# WRIST.net
KiCad netlist of a schematic drawn in EAGLE
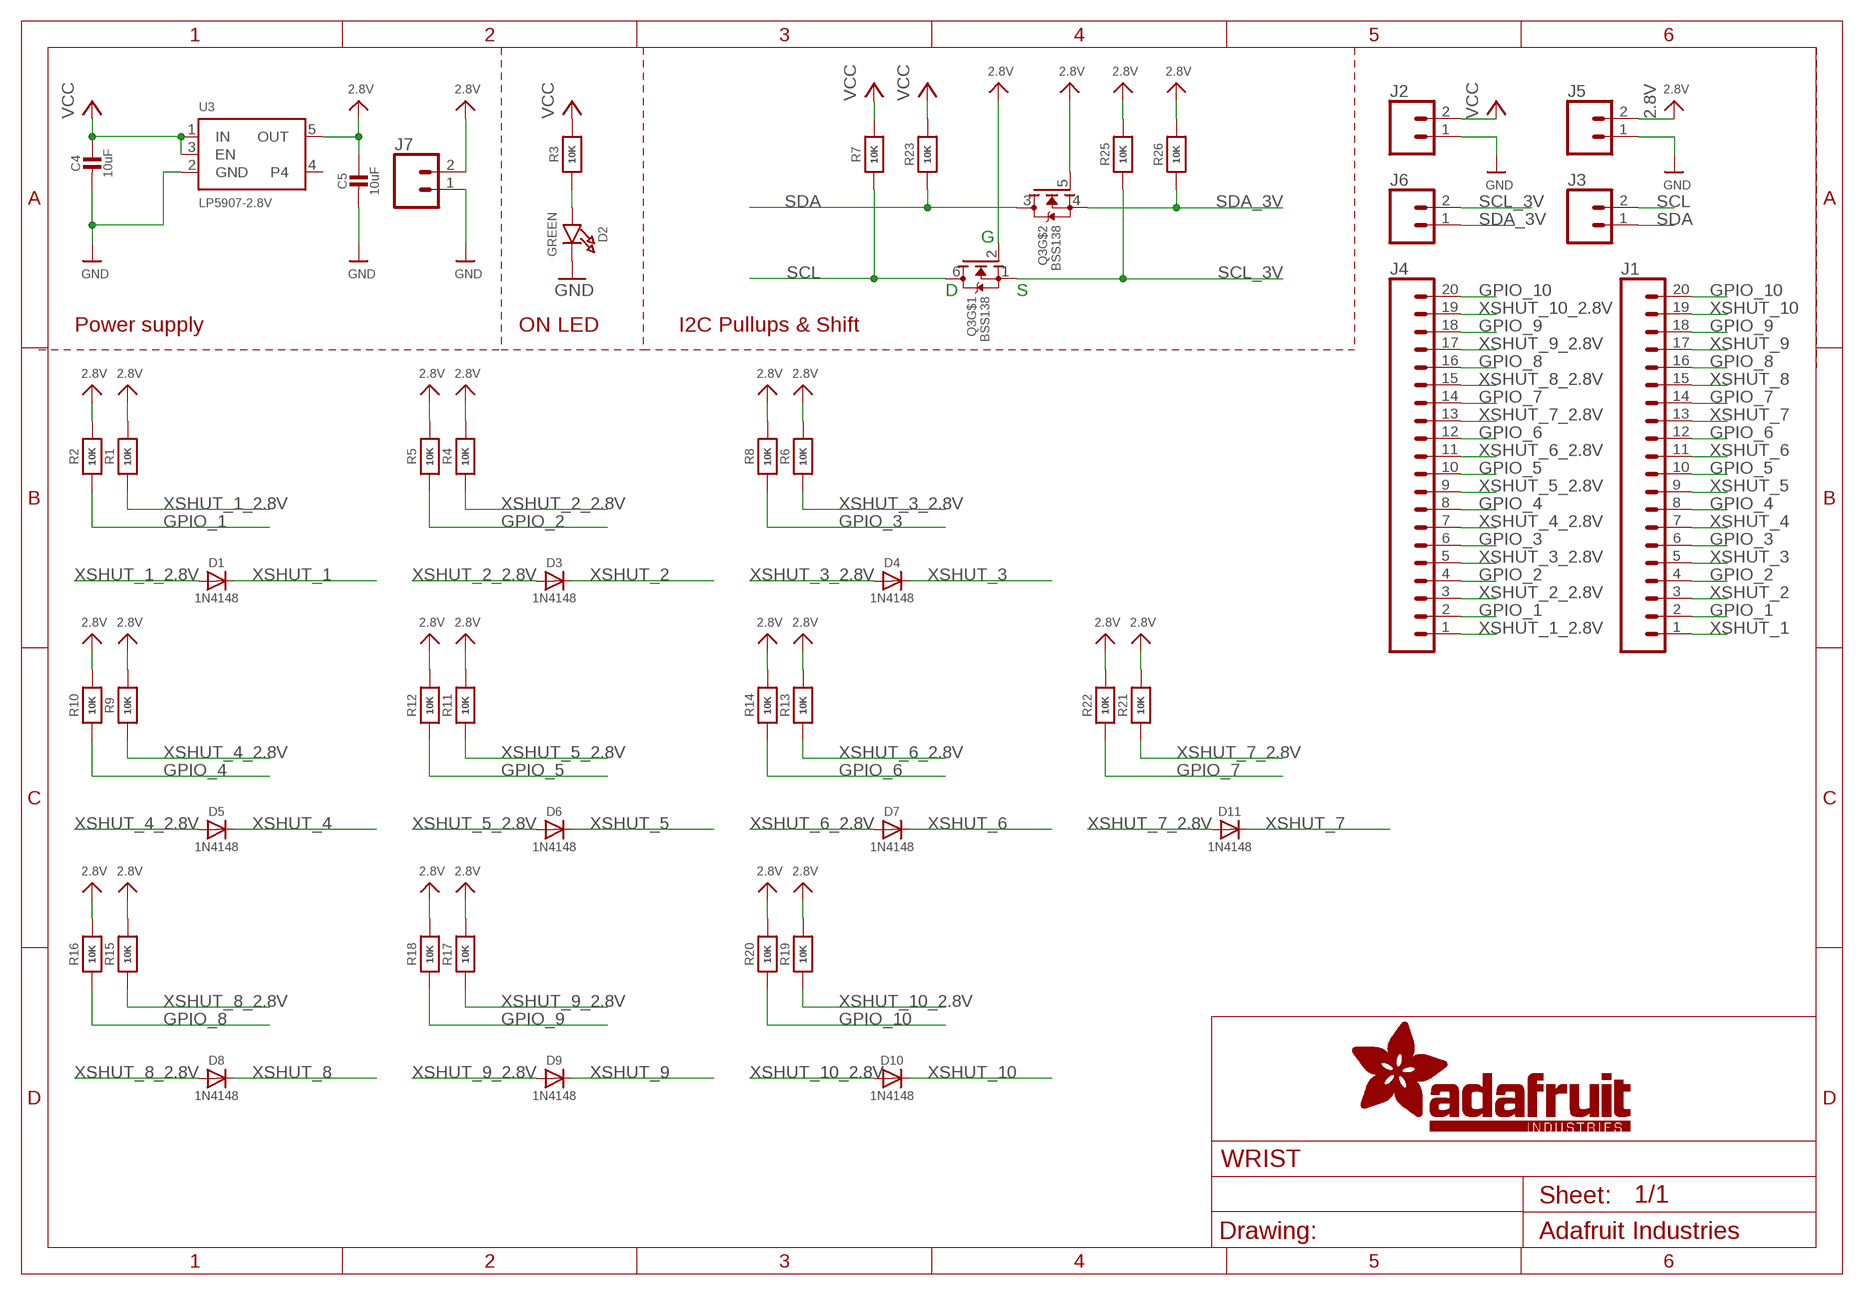
[diagram p0: schematic, sheet 1]

(export (version "E")
  (design (tool "Eeschema 10.0.6"))
  (components
    (comp (ref "C4")
      (value "10uF")
      (footprint "eagle-import:0805-NO")
      (libsource (lib "eagle-import") (part "CAP_CERAMIC0805-NOOUTLINE"))
    )
    (comp (ref "C5")
      (value "10uF")
      (footprint "eagle-import:0805-NO")
      (libsource (lib "eagle-import") (part "CAP_CERAMIC0805-NOOUTLINE"))
    )
    (comp (ref "D1")
      (value "1N4148")
      (footprint "eagle-import:SOD-323")
      (libsource (lib "eagle-import") (part "DIODESOD-323"))
    )
    (comp (ref "D2")
      (value "GREEN")
      (footprint "eagle-import:CHIPLED_0603_NOOUTLINE")
      (libsource (lib "eagle-import") (part "LED0603_NOOUTLINE"))
    )
    (comp (ref "D3")
      (value "1N4148")
      (footprint "eagle-import:SOD-323")
      (libsource (lib "eagle-import") (part "DIODESOD-323"))
    )
    (comp (ref "D4")
      (value "1N4148")
      (footprint "eagle-import:SOD-323")
      (libsource (lib "eagle-import") (part "DIODESOD-323"))
    )
    (comp (ref "D5")
      (value "1N4148")
      (footprint "eagle-import:SOD-323")
      (libsource (lib "eagle-import") (part "DIODESOD-323"))
    )
    (comp (ref "D6")
      (value "1N4148")
      (footprint "eagle-import:SOD-323")
      (libsource (lib "eagle-import") (part "DIODESOD-323"))
    )
    (comp (ref "D7")
      (value "1N4148")
      (footprint "eagle-import:SOD-323")
      (libsource (lib "eagle-import") (part "DIODESOD-323"))
    )
    (comp (ref "D8")
      (value "1N4148")
      (footprint "eagle-import:SOD-323")
      (libsource (lib "eagle-import") (part "DIODESOD-323"))
    )
    (comp (ref "D9")
      (value "1N4148")
      (footprint "eagle-import:SOD-323")
      (libsource (lib "eagle-import") (part "DIODESOD-323"))
    )
    (comp (ref "D10")
      (value "1N4148")
      (footprint "eagle-import:SOD-323")
      (libsource (lib "eagle-import") (part "DIODESOD-323"))
    )
    (comp (ref "D11")
      (value "1N4148")
      (footprint "eagle-import:SOD-323")
      (libsource (lib "eagle-import") (part "DIODESOD-323"))
    )
    (comp (ref "J1")
      (value "CONN_20NOSILK")
      (footprint "eagle-import:1X20_NOSILK")
      (libsource (lib "eagle-import") (part "CONN_20NOSILK"))
    )
    (comp (ref "J2")
      (value "CONN_021X02_NO_SILK")
      (footprint "eagle-import:1X02_NO_SILK")
      (libsource (lib "eagle-import") (part "CONN_021X02_NO_SILK"))
    )
    (comp (ref "J3")
      (value "CONN_021X02_NO_SILK")
      (footprint "eagle-import:1X02_NO_SILK")
      (libsource (lib "eagle-import") (part "CONN_021X02_NO_SILK"))
    )
    (comp (ref "J4")
      (value "CONN_20NOSILK")
      (footprint "eagle-import:1X20_NOSILK")
      (libsource (lib "eagle-import") (part "CONN_20NOSILK"))
    )
    (comp (ref "J5")
      (value "CONN_021X02_NO_SILK")
      (footprint "eagle-import:1X02_NO_SILK")
      (libsource (lib "eagle-import") (part "CONN_021X02_NO_SILK"))
    )
    (comp (ref "J6")
      (value "CONN_021X02_NO_SILK")
      (footprint "eagle-import:1X02_NO_SILK")
      (libsource (lib "eagle-import") (part "CONN_021X02_NO_SILK"))
    )
    (comp (ref "J7")
      (value "CONN_021X02_NO_SILK")
      (footprint "eagle-import:1X02_NO_SILK")
      (libsource (lib "eagle-import") (part "CONN_021X02_NO_SILK"))
    )
    (comp (ref "Q3")
      (value "BSS138")
      (footprint "eagle-import:SOT363")
      (libsource (lib "eagle-import") (part "MOSFET-N_DUAL"))
    )
    (comp (ref "R1")
      (value "10K")
      (footprint "eagle-import:0603-NO")
      (libsource (lib "eagle-import") (part "RESISTOR_0603_NOOUT"))
    )
    (comp (ref "R2")
      (value "10K")
      (footprint "eagle-import:0603-NO")
      (libsource (lib "eagle-import") (part "RESISTOR_0603_NOOUT"))
    )
    (comp (ref "R3")
      (value "10K")
      (footprint "eagle-import:0603-NO")
      (libsource (lib "eagle-import") (part "RESISTOR_0603_NOOUT"))
    )
    (comp (ref "R4")
      (value "10K")
      (footprint "eagle-import:0603-NO")
      (libsource (lib "eagle-import") (part "RESISTOR_0603_NOOUT"))
    )
    (comp (ref "R5")
      (value "10K")
      (footprint "eagle-import:0603-NO")
      (libsource (lib "eagle-import") (part "RESISTOR_0603_NOOUT"))
    )
    (comp (ref "R6")
      (value "10K")
      (footprint "eagle-import:0603-NO")
      (libsource (lib "eagle-import") (part "RESISTOR_0603_NOOUT"))
    )
    (comp (ref "R7")
      (value "10K")
      (footprint "eagle-import:0603-NO")
      (libsource (lib "eagle-import") (part "RESISTOR_0603_NOOUT"))
    )
    (comp (ref "R8")
      (value "10K")
      (footprint "eagle-import:0603-NO")
      (libsource (lib "eagle-import") (part "RESISTOR_0603_NOOUT"))
    )
    (comp (ref "R9")
      (value "10K")
      (footprint "eagle-import:0603-NO")
      (libsource (lib "eagle-import") (part "RESISTOR_0603_NOOUT"))
    )
    (comp (ref "R10")
      (value "10K")
      (footprint "eagle-import:0603-NO")
      (libsource (lib "eagle-import") (part "RESISTOR_0603_NOOUT"))
    )
    (comp (ref "R11")
      (value "10K")
      (footprint "eagle-import:0603-NO")
      (libsource (lib "eagle-import") (part "RESISTOR_0603_NOOUT"))
    )
    (comp (ref "R12")
      (value "10K")
      (footprint "eagle-import:0603-NO")
      (libsource (lib "eagle-import") (part "RESISTOR_0603_NOOUT"))
    )
    (comp (ref "R13")
      (value "10K")
      (footprint "eagle-import:0603-NO")
      (libsource (lib "eagle-import") (part "RESISTOR_0603_NOOUT"))
    )
    (comp (ref "R14")
      (value "10K")
      (footprint "eagle-import:0603-NO")
      (libsource (lib "eagle-import") (part "RESISTOR_0603_NOOUT"))
    )
    (comp (ref "R15")
      (value "10K")
      (footprint "eagle-import:0603-NO")
      (libsource (lib "eagle-import") (part "RESISTOR_0603_NOOUT"))
    )
    (comp (ref "R16")
      (value "10K")
      (footprint "eagle-import:0603-NO")
      (libsource (lib "eagle-import") (part "RESISTOR_0603_NOOUT"))
    )
    (comp (ref "R17")
      (value "10K")
      (footprint "eagle-import:0603-NO")
      (libsource (lib "eagle-import") (part "RESISTOR_0603_NOOUT"))
    )
    (comp (ref "R18")
      (value "10K")
      (footprint "eagle-import:0603-NO")
      (libsource (lib "eagle-import") (part "RESISTOR_0603_NOOUT"))
    )
    (comp (ref "R19")
      (value "10K")
      (footprint "eagle-import:0603-NO")
      (libsource (lib "eagle-import") (part "RESISTOR_0603_NOOUT"))
    )
    (comp (ref "R20")
      (value "10K")
      (footprint "eagle-import:0603-NO")
      (libsource (lib "eagle-import") (part "RESISTOR_0603_NOOUT"))
    )
    (comp (ref "R21")
      (value "10K")
      (footprint "eagle-import:0603-NO")
      (libsource (lib "eagle-import") (part "RESISTOR_0603_NOOUT"))
    )
    (comp (ref "R22")
      (value "10K")
      (footprint "eagle-import:0603-NO")
      (libsource (lib "eagle-import") (part "RESISTOR_0603_NOOUT"))
    )
    (comp (ref "R23")
      (value "10K")
      (footprint "eagle-import:0603-NO")
      (libsource (lib "eagle-import") (part "RESISTOR_0603_NOOUT"))
    )
    (comp (ref "R25")
      (value "10K")
      (footprint "eagle-import:0603-NO")
      (libsource (lib "eagle-import") (part "RESISTOR_0603_NOOUT"))
    )
    (comp (ref "R26")
      (value "10K")
      (footprint "eagle-import:0603-NO")
      (libsource (lib "eagle-import") (part "RESISTOR_0603_NOOUT"))
    )
    (comp (ref "U3")
      (value "LP5907-2.8V")
      (footprint "eagle-import:SOT23-5")
      (libsource (lib "eagle-import") (part "VREG_SOT23-5"))
    )
  )
  (nets
    (net (code "1") (name "/GPIO_1") (class "Default")
      (node (ref "J1") (pin "2") (pinfunction "2_2") (pintype "passive"))
      (node (ref "J4") (pin "2") (pinfunction "2_2") (pintype "passive"))
      (node (ref "R2") (pin "1") (pinfunction "1_1") (pintype "passive"))
    )
    (net (code "2") (name "/GPIO_2") (class "Default")
      (node (ref "J1") (pin "4") (pinfunction "4_4") (pintype "passive"))
      (node (ref "J4") (pin "4") (pinfunction "4_4") (pintype "passive"))
      (node (ref "R5") (pin "1") (pinfunction "1_1") (pintype "passive"))
    )
    (net (code "3") (name "/GPIO_3") (class "Default")
      (node (ref "J1") (pin "6") (pinfunction "6_6") (pintype "passive"))
      (node (ref "J4") (pin "6") (pinfunction "6_6") (pintype "passive"))
      (node (ref "R8") (pin "1") (pinfunction "1_1") (pintype "passive"))
    )
    (net (code "4") (name "/GPIO_4") (class "Default")
      (node (ref "J1") (pin "8") (pinfunction "8_8") (pintype "passive"))
      (node (ref "J4") (pin "8") (pinfunction "8_8") (pintype "passive"))
      (node (ref "R10") (pin "1") (pinfunction "1_1") (pintype "passive"))
    )
    (net (code "5") (name "/GPIO_5") (class "Default")
      (node (ref "J1") (pin "10") (pinfunction "10_10") (pintype "passive"))
      (node (ref "J4") (pin "10") (pinfunction "10_10") (pintype "passive"))
      (node (ref "R12") (pin "1") (pinfunction "1_1") (pintype "passive"))
    )
    (net (code "6") (name "/GPIO_6") (class "Default")
      (node (ref "J1") (pin "12") (pinfunction "12_12") (pintype "passive"))
      (node (ref "J4") (pin "12") (pinfunction "12_12") (pintype "passive"))
      (node (ref "R14") (pin "1") (pinfunction "1_1") (pintype "passive"))
    )
    (net (code "7") (name "/GPIO_7") (class "Default")
      (node (ref "J1") (pin "14") (pinfunction "14_14") (pintype "passive"))
      (node (ref "J4") (pin "14") (pinfunction "14_14") (pintype "passive"))
      (node (ref "R22") (pin "1") (pinfunction "1_1") (pintype "passive"))
    )
    (net (code "8") (name "/GPIO_8") (class "Default")
      (node (ref "J1") (pin "16") (pinfunction "16_16") (pintype "passive"))
      (node (ref "J4") (pin "16") (pinfunction "16_16") (pintype "passive"))
      (node (ref "R16") (pin "1") (pinfunction "1_1") (pintype "passive"))
    )
    (net (code "9") (name "/GPIO_9") (class "Default")
      (node (ref "J1") (pin "18") (pinfunction "18_18") (pintype "passive"))
      (node (ref "J4") (pin "18") (pinfunction "18_18") (pintype "passive"))
      (node (ref "R18") (pin "1") (pinfunction "1_1") (pintype "passive"))
    )
    (net (code "10") (name "/GPIO_10") (class "Default")
      (node (ref "J1") (pin "20") (pinfunction "20_20") (pintype "passive"))
      (node (ref "J4") (pin "20") (pinfunction "20_20") (pintype "passive"))
      (node (ref "R20") (pin "1") (pinfunction "1_1") (pintype "passive"))
    )
    (net (code "11") (name "/SCL") (class "Default")
      (node (ref "J3") (pin "2") (pinfunction "2_2") (pintype "passive"))
      (node (ref "Q3") (pin "6") (pinfunction "D_6") (pintype "bidirectional"))
      (node (ref "R7") (pin "1") (pinfunction "1_1") (pintype "passive"))
    )
    (net (code "12") (name "/SCL_3V") (class "Default")
      (node (ref "J6") (pin "2") (pinfunction "2_2") (pintype "passive"))
      (node (ref "Q3") (pin "1") (pinfunction "S_1") (pintype "bidirectional"))
      (node (ref "R25") (pin "1") (pinfunction "1_1") (pintype "passive"))
    )
    (net (code "13") (name "/SDA") (class "Default")
      (node (ref "J3") (pin "1") (pinfunction "1_1") (pintype "passive"))
      (node (ref "Q3") (pin "3") (pinfunction "D_3") (pintype "bidirectional"))
      (node (ref "R23") (pin "1") (pinfunction "1_1") (pintype "passive"))
    )
    (net (code "14") (name "/SDA_3V") (class "Default")
      (node (ref "J6") (pin "1") (pinfunction "1_1") (pintype "passive"))
      (node (ref "Q3") (pin "4") (pinfunction "S_4") (pintype "bidirectional"))
      (node (ref "R26") (pin "1") (pinfunction "1_1") (pintype "passive"))
    )
    (net (code "15") (name "/XSHUT_1") (class "Default")
      (node (ref "D1") (pin "C") (pinfunction "C_C") (pintype "passive"))
      (node (ref "J1") (pin "1") (pinfunction "1_1") (pintype "passive"))
    )
    (net (code "16") (name "/XSHUT_1_2.8V") (class "Default")
      (node (ref "D1") (pin "A") (pinfunction "A_A") (pintype "passive"))
      (node (ref "J4") (pin "1") (pinfunction "1_1") (pintype "passive"))
      (node (ref "R1") (pin "1") (pinfunction "1_1") (pintype "passive"))
    )
    (net (code "17") (name "/XSHUT_2") (class "Default")
      (node (ref "D3") (pin "C") (pinfunction "C_C") (pintype "passive"))
      (node (ref "J1") (pin "3") (pinfunction "3_3") (pintype "passive"))
    )
    (net (code "18") (name "/XSHUT_2_2.8V") (class "Default")
      (node (ref "D3") (pin "A") (pinfunction "A_A") (pintype "passive"))
      (node (ref "J4") (pin "3") (pinfunction "3_3") (pintype "passive"))
      (node (ref "R4") (pin "1") (pinfunction "1_1") (pintype "passive"))
    )
    (net (code "19") (name "/XSHUT_3") (class "Default")
      (node (ref "D4") (pin "C") (pinfunction "C_C") (pintype "passive"))
      (node (ref "J1") (pin "5") (pinfunction "5_5") (pintype "passive"))
    )
    (net (code "20") (name "/XSHUT_3_2.8V") (class "Default")
      (node (ref "D4") (pin "A") (pinfunction "A_A") (pintype "passive"))
      (node (ref "J4") (pin "5") (pinfunction "5_5") (pintype "passive"))
      (node (ref "R6") (pin "1") (pinfunction "1_1") (pintype "passive"))
    )
    (net (code "21") (name "/XSHUT_4") (class "Default")
      (node (ref "D5") (pin "C") (pinfunction "C_C") (pintype "passive"))
      (node (ref "J1") (pin "7") (pinfunction "7_7") (pintype "passive"))
    )
    (net (code "22") (name "/XSHUT_4_2.8V") (class "Default")
      (node (ref "D5") (pin "A") (pinfunction "A_A") (pintype "passive"))
      (node (ref "J4") (pin "7") (pinfunction "7_7") (pintype "passive"))
      (node (ref "R9") (pin "1") (pinfunction "1_1") (pintype "passive"))
    )
    (net (code "23") (name "/XSHUT_5") (class "Default")
      (node (ref "D6") (pin "C") (pinfunction "C_C") (pintype "passive"))
      (node (ref "J1") (pin "9") (pinfunction "9_9") (pintype "passive"))
    )
    (net (code "24") (name "/XSHUT_5_2.8V") (class "Default")
      (node (ref "D6") (pin "A") (pinfunction "A_A") (pintype "passive"))
      (node (ref "J4") (pin "9") (pinfunction "9_9") (pintype "passive"))
      (node (ref "R11") (pin "1") (pinfunction "1_1") (pintype "passive"))
    )
    (net (code "25") (name "/XSHUT_6") (class "Default")
      (node (ref "D7") (pin "C") (pinfunction "C_C") (pintype "passive"))
      (node (ref "J1") (pin "11") (pinfunction "11_11") (pintype "passive"))
    )
    (net (code "26") (name "/XSHUT_6_2.8V") (class "Default")
      (node (ref "D7") (pin "A") (pinfunction "A_A") (pintype "passive"))
      (node (ref "J4") (pin "11") (pinfunction "11_11") (pintype "passive"))
      (node (ref "R13") (pin "1") (pinfunction "1_1") (pintype "passive"))
    )
    (net (code "27") (name "/XSHUT_7") (class "Default")
      (node (ref "D11") (pin "C") (pinfunction "C_C") (pintype "passive"))
      (node (ref "J1") (pin "13") (pinfunction "13_13") (pintype "passive"))
    )
    (net (code "28") (name "/XSHUT_7_2.8V") (class "Default")
      (node (ref "D11") (pin "A") (pinfunction "A_A") (pintype "passive"))
      (node (ref "J4") (pin "13") (pinfunction "13_13") (pintype "passive"))
      (node (ref "R21") (pin "1") (pinfunction "1_1") (pintype "passive"))
    )
    (net (code "29") (name "/XSHUT_8") (class "Default")
      (node (ref "D8") (pin "C") (pinfunction "C_C") (pintype "passive"))
      (node (ref "J1") (pin "15") (pinfunction "15_15") (pintype "passive"))
    )
    (net (code "30") (name "/XSHUT_8_2.8V") (class "Default")
      (node (ref "D8") (pin "A") (pinfunction "A_A") (pintype "passive"))
      (node (ref "J4") (pin "15") (pinfunction "15_15") (pintype "passive"))
      (node (ref "R15") (pin "1") (pinfunction "1_1") (pintype "passive"))
    )
    (net (code "31") (name "/XSHUT_9") (class "Default")
      (node (ref "D9") (pin "C") (pinfunction "C_C") (pintype "passive"))
      (node (ref "J1") (pin "17") (pinfunction "17_17") (pintype "passive"))
    )
    (net (code "32") (name "/XSHUT_9_2.8V") (class "Default")
      (node (ref "D9") (pin "A") (pinfunction "A_A") (pintype "passive"))
      (node (ref "J4") (pin "17") (pinfunction "17_17") (pintype "passive"))
      (node (ref "R17") (pin "1") (pinfunction "1_1") (pintype "passive"))
    )
    (net (code "33") (name "/XSHUT_10") (class "Default")
      (node (ref "D10") (pin "C") (pinfunction "C_C") (pintype "passive"))
      (node (ref "J1") (pin "19") (pinfunction "19_19") (pintype "passive"))
    )
    (net (code "34") (name "/XSHUT_10_2.8V") (class "Default")
      (node (ref "D10") (pin "A") (pinfunction "A_A") (pintype "passive"))
      (node (ref "J4") (pin "19") (pinfunction "19_19") (pintype "passive"))
      (node (ref "R19") (pin "1") (pinfunction "1_1") (pintype "passive"))
    )
    (net (code "35") (name "2.8V") (class "Default")
      (node (ref "C5") (pin "1") (pinfunction "1_1") (pintype "passive"))
      (node (ref "J5") (pin "2") (pinfunction "2_2") (pintype "passive"))
      (node (ref "J7") (pin "2") (pinfunction "2_2") (pintype "passive"))
      (node (ref "Q3") (pin "2") (pinfunction "G_2") (pintype "bidirectional"))
      (node (ref "Q3") (pin "5") (pinfunction "G_5") (pintype "bidirectional"))
      (node (ref "R1") (pin "2") (pinfunction "2_2") (pintype "passive"))
      (node (ref "R10") (pin "2") (pinfunction "2_2") (pintype "passive"))
      (node (ref "R11") (pin "2") (pinfunction "2_2") (pintype "passive"))
      (node (ref "R12") (pin "2") (pinfunction "2_2") (pintype "passive"))
      (node (ref "R13") (pin "2") (pinfunction "2_2") (pintype "passive"))
      (node (ref "R14") (pin "2") (pinfunction "2_2") (pintype "passive"))
      (node (ref "R15") (pin "2") (pinfunction "2_2") (pintype "passive"))
      (node (ref "R16") (pin "2") (pinfunction "2_2") (pintype "passive"))
      (node (ref "R17") (pin "2") (pinfunction "2_2") (pintype "passive"))
      (node (ref "R18") (pin "2") (pinfunction "2_2") (pintype "passive"))
      (node (ref "R19") (pin "2") (pinfunction "2_2") (pintype "passive"))
      (node (ref "R2") (pin "2") (pinfunction "2_2") (pintype "passive"))
      (node (ref "R20") (pin "2") (pinfunction "2_2") (pintype "passive"))
      (node (ref "R21") (pin "2") (pinfunction "2_2") (pintype "passive"))
      (node (ref "R22") (pin "2") (pinfunction "2_2") (pintype "passive"))
      (node (ref "R25") (pin "2") (pinfunction "2_2") (pintype "passive"))
      (node (ref "R26") (pin "2") (pinfunction "2_2") (pintype "passive"))
      (node (ref "R4") (pin "2") (pinfunction "2_2") (pintype "passive"))
      (node (ref "R5") (pin "2") (pinfunction "2_2") (pintype "passive"))
      (node (ref "R6") (pin "2") (pinfunction "2_2") (pintype "passive"))
      (node (ref "R8") (pin "2") (pinfunction "2_2") (pintype "passive"))
      (node (ref "R9") (pin "2") (pinfunction "2_2") (pintype "passive"))
      (node (ref "U3") (pin "5") (pinfunction "OUT_5") (pintype "power_in"))
    )
    (net (code "36") (name "GND") (class "Default")
      (node (ref "C4") (pin "2") (pinfunction "2_2") (pintype "passive"))
      (node (ref "C5") (pin "2") (pinfunction "2_2") (pintype "passive"))
      (node (ref "D2") (pin "C") (pinfunction "C_C") (pintype "passive"))
      (node (ref "J2") (pin "1") (pinfunction "1_1") (pintype "passive"))
      (node (ref "J5") (pin "1") (pinfunction "1_1") (pintype "passive"))
      (node (ref "J7") (pin "1") (pinfunction "1_1") (pintype "passive"))
      (node (ref "U3") (pin "2") (pinfunction "GND_2") (pintype "power_in"))
    )
    (net (code "37") (name "Net-(D2-PadA)") (class "Default")
      (node (ref "D2") (pin "A") (pinfunction "A_A") (pintype "passive"))
      (node (ref "R3") (pin "1") (pinfunction "1_1") (pintype "passive"))
    )
    (net (code "38") (name "VCC") (class "Default")
      (node (ref "C4") (pin "1") (pinfunction "1_1") (pintype "passive"))
      (node (ref "J2") (pin "2") (pinfunction "2_2") (pintype "passive"))
      (node (ref "R23") (pin "2") (pinfunction "2_2") (pintype "passive"))
      (node (ref "R3") (pin "2") (pinfunction "2_2") (pintype "passive"))
      (node (ref "R7") (pin "2") (pinfunction "2_2") (pintype "passive"))
      (node (ref "U3") (pin "1") (pinfunction "IN_1") (pintype "power_in"))
      (node (ref "U3") (pin "3") (pinfunction "EN_3") (pintype "input"))
    )
    (net (code "39") (name "unconnected-(U3-P4-Pad4)") (class "Default")
      (node (ref "U3") (pin "4") (pinfunction "P4_4") (pintype "bidirectional"))
    )
  )
)
